# seismometer_sensorboard.net
KiCad netlist of a schematic drawn in EAGLE
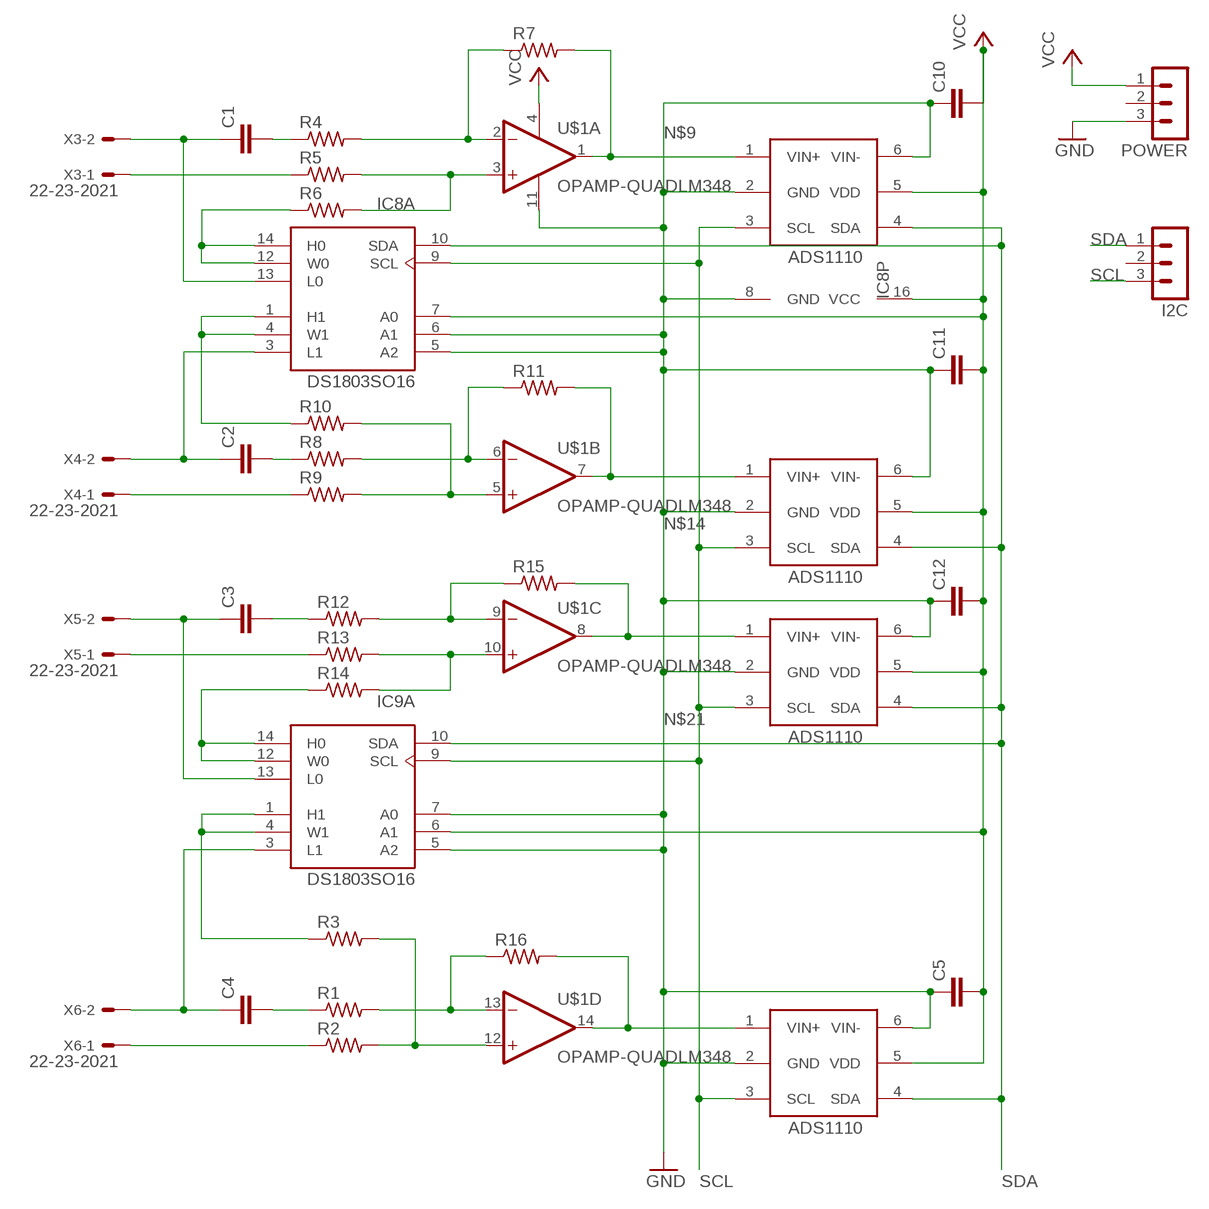
[diagram p0: schematic, sheet 1]

(export (version "E")
  (design (tool "Eeschema 10.0.6"))
  (components
    (comp (ref "C1")
      (value "C-EU025-030X050")
      (footprint "eagle-import:C025-030X050")
      (libsource (lib "eagle-import") (part "C-EU025-030X050"))
    )
    (comp (ref "C2")
      (value "C-EU025-030X050")
      (footprint "eagle-import:C025-030X050")
      (libsource (lib "eagle-import") (part "C-EU025-030X050"))
    )
    (comp (ref "C3")
      (value "C-EU025-030X050")
      (footprint "eagle-import:C025-030X050")
      (libsource (lib "eagle-import") (part "C-EU025-030X050"))
    )
    (comp (ref "C4")
      (value "C-EU025-030X050")
      (footprint "eagle-import:C025-030X050")
      (libsource (lib "eagle-import") (part "C-EU025-030X050"))
    )
    (comp (ref "C5")
      (value "C-EU025-030X050")
      (footprint "eagle-import:C025-030X050")
      (libsource (lib "eagle-import") (part "C-EU025-030X050"))
    )
    (comp (ref "C10")
      (value "C-EU025-030X050")
      (footprint "eagle-import:C025-030X050")
      (libsource (lib "eagle-import") (part "C-EU025-030X050"))
    )
    (comp (ref "C11")
      (value "C-EU025-030X050")
      (footprint "eagle-import:C025-030X050")
      (libsource (lib "eagle-import") (part "C-EU025-030X050"))
    )
    (comp (ref "C12")
      (value "C-EU025-030X050")
      (footprint "eagle-import:C025-030X050")
      (libsource (lib "eagle-import") (part "C-EU025-030X050"))
    )
    (comp (ref "I2C")
      (value "MA03-1")
      (footprint "eagle-import:MA03-1")
      (libsource (lib "eagle-import") (part "MA03-1"))
    )
    (comp (ref "IC1")
      (value "ADS1110")
      (footprint "eagle-import:SOT-23-6")
      (libsource (lib "eagle-import") (part "ADS1110"))
    )
    (comp (ref "IC4")
      (value "ADS1110")
      (footprint "eagle-import:SOT-23-6")
      (libsource (lib "eagle-import") (part "ADS1110"))
    )
    (comp (ref "IC5")
      (value "ADS1110")
      (footprint "eagle-import:SOT-23-6")
      (libsource (lib "eagle-import") (part "ADS1110"))
    )
    (comp (ref "IC6")
      (value "ADS1110")
      (footprint "eagle-import:SOT-23-6")
      (libsource (lib "eagle-import") (part "ADS1110"))
    )
    (comp (ref "IC8")
      (value "DS1803SO16")
      (footprint "eagle-import:SO16")
      (libsource (lib "eagle-import") (part "DS1803?SO16"))
    )
    (comp (ref "IC9")
      (value "DS1803SO16")
      (footprint "eagle-import:SO16")
      (libsource (lib "eagle-import") (part "DS1803?SO16"))
    )
    (comp (ref "POWER")
      (value "MA03-1")
      (footprint "eagle-import:MA03-1")
      (libsource (lib "eagle-import") (part "MA03-1"))
    )
    (comp (ref "R1")
      (value "R-US_0207/12")
      (footprint "eagle-import:0207_12")
      (libsource (lib "eagle-import") (part "R-US_0207/12"))
    )
    (comp (ref "R2")
      (value "R-US_0207/12")
      (footprint "eagle-import:0207_12")
      (libsource (lib "eagle-import") (part "R-US_0207/12"))
    )
    (comp (ref "R3")
      (value "R-US_0207/12")
      (footprint "eagle-import:0207_12")
      (libsource (lib "eagle-import") (part "R-US_0207/12"))
    )
    (comp (ref "R4")
      (value "R-US_0207/12")
      (footprint "eagle-import:0207_12")
      (libsource (lib "eagle-import") (part "R-US_0207/12"))
    )
    (comp (ref "R5")
      (value "R-US_0207/12")
      (footprint "eagle-import:0207_12")
      (libsource (lib "eagle-import") (part "R-US_0207/12"))
    )
    (comp (ref "R6")
      (value "R-US_0207/12")
      (footprint "eagle-import:0207_12")
      (libsource (lib "eagle-import") (part "R-US_0207/12"))
    )
    (comp (ref "R7")
      (value "R-US_0207/12")
      (footprint "eagle-import:0207_12")
      (libsource (lib "eagle-import") (part "R-US_0207/12"))
    )
    (comp (ref "R8")
      (value "R-US_0207/12")
      (footprint "eagle-import:0207_12")
      (libsource (lib "eagle-import") (part "R-US_0207/12"))
    )
    (comp (ref "R9")
      (value "R-US_0207/12")
      (footprint "eagle-import:0207_12")
      (libsource (lib "eagle-import") (part "R-US_0207/12"))
    )
    (comp (ref "R10")
      (value "R-US_0207/12")
      (footprint "eagle-import:0207_12")
      (libsource (lib "eagle-import") (part "R-US_0207/12"))
    )
    (comp (ref "R11")
      (value "R-US_0207/12")
      (footprint "eagle-import:0207_12")
      (libsource (lib "eagle-import") (part "R-US_0207/12"))
    )
    (comp (ref "R12")
      (value "R-US_0207/12")
      (footprint "eagle-import:0207_12")
      (libsource (lib "eagle-import") (part "R-US_0207/12"))
    )
    (comp (ref "R13")
      (value "R-US_0207/12")
      (footprint "eagle-import:0207_12")
      (libsource (lib "eagle-import") (part "R-US_0207/12"))
    )
    (comp (ref "R14")
      (value "R-US_0207/12")
      (footprint "eagle-import:0207_12")
      (libsource (lib "eagle-import") (part "R-US_0207/12"))
    )
    (comp (ref "R15")
      (value "R-US_0207/12")
      (footprint "eagle-import:0207_12")
      (libsource (lib "eagle-import") (part "R-US_0207/12"))
    )
    (comp (ref "R16")
      (value "R-US_0207/12")
      (footprint "eagle-import:0207_12")
      (libsource (lib "eagle-import") (part "R-US_0207/12"))
    )
    (comp (ref "U$1")
      (value "OPAMP-QUADLM348")
      (footprint "eagle-import:DIP14")
      (libsource (lib "eagle-import") (part "OPAMP-QUADLM348"))
    )
    (comp (ref "X3")
      (value "22-23-2021")
      (footprint "eagle-import:22-23-2021")
      (fields (field (name "MF") "MOLEX"))
      (libsource (lib "eagle-import") (part "22-23-2021"))
    )
    (comp (ref "X4")
      (value "22-23-2021")
      (footprint "eagle-import:22-23-2021")
      (fields (field (name "MF") "MOLEX"))
      (libsource (lib "eagle-import") (part "22-23-2021"))
    )
    (comp (ref "X5")
      (value "22-23-2021")
      (footprint "eagle-import:22-23-2021")
      (fields (field (name "MF") "MOLEX"))
      (libsource (lib "eagle-import") (part "22-23-2021"))
    )
    (comp (ref "X6")
      (value "22-23-2021")
      (footprint "eagle-import:22-23-2021")
      (fields (field (name "MF") "MOLEX"))
      (libsource (lib "eagle-import") (part "22-23-2021"))
    )
  )
  (nets
    (net (code "1") (name "/N$9") (class "Default")
      (node (ref "IC4") (pin "1") (pinfunction "VIN+_1") (pintype "bidirectional"))
      (node (ref "R7") (pin "2") (pinfunction "2_2") (pintype "passive"))
      (node (ref "U$1") (pin "1") (pinfunction "OUT_1") (pintype "output"))
    )
    (net (code "2") (name "/N$14") (class "Default")
      (node (ref "IC5") (pin "1") (pinfunction "VIN+_1") (pintype "bidirectional"))
      (node (ref "R11") (pin "2") (pinfunction "2_2") (pintype "passive"))
      (node (ref "U$1") (pin "7") (pinfunction "OUT_7") (pintype "output"))
    )
    (net (code "3") (name "/N$21") (class "Default")
      (node (ref "IC6") (pin "1") (pinfunction "VIN+_1") (pintype "bidirectional"))
      (node (ref "R15") (pin "2") (pinfunction "2_2") (pintype "passive"))
      (node (ref "U$1") (pin "8") (pinfunction "OUT_8") (pintype "output"))
    )
    (net (code "4") (name "/SCL") (class "Default")
      (node (ref "I2C") (pin "3") (pinfunction "3_3") (pintype "passive"))
      (node (ref "IC1") (pin "3") (pinfunction "SCL_3") (pintype "bidirectional"))
      (node (ref "IC4") (pin "3") (pinfunction "SCL_3") (pintype "bidirectional"))
      (node (ref "IC5") (pin "3") (pinfunction "SCL_3") (pintype "bidirectional"))
      (node (ref "IC6") (pin "3") (pinfunction "SCL_3") (pintype "bidirectional"))
      (node (ref "IC8") (pin "9") (pinfunction "SCL_9") (pintype "input"))
      (node (ref "IC9") (pin "9") (pinfunction "SCL_9") (pintype "input"))
    )
    (net (code "5") (name "/SDA") (class "Default")
      (node (ref "I2C") (pin "1") (pinfunction "1_1") (pintype "passive"))
      (node (ref "IC1") (pin "4") (pinfunction "SDA_4") (pintype "bidirectional"))
      (node (ref "IC4") (pin "4") (pinfunction "SDA_4") (pintype "bidirectional"))
      (node (ref "IC5") (pin "4") (pinfunction "SDA_4") (pintype "bidirectional"))
      (node (ref "IC6") (pin "4") (pinfunction "SDA_4") (pintype "bidirectional"))
      (node (ref "IC8") (pin "10") (pinfunction "SDA_10") (pintype "bidirectional"))
      (node (ref "IC9") (pin "10") (pinfunction "SDA_10") (pintype "bidirectional"))
    )
    (net (code "6") (name "GND") (class "Default")
      (node (ref "C10") (pin "1") (pinfunction "1_1") (pintype "passive"))
      (node (ref "C11") (pin "1") (pinfunction "1_1") (pintype "passive"))
      (node (ref "C12") (pin "1") (pinfunction "1_1") (pintype "passive"))
      (node (ref "C5") (pin "1") (pinfunction "1_1") (pintype "passive"))
      (node (ref "IC1") (pin "2") (pinfunction "GND_2") (pintype "bidirectional"))
      (node (ref "IC1") (pin "6") (pinfunction "VIN-_6") (pintype "bidirectional"))
      (node (ref "IC4") (pin "2") (pinfunction "GND_2") (pintype "bidirectional"))
      (node (ref "IC4") (pin "6") (pinfunction "VIN-_6") (pintype "bidirectional"))
      (node (ref "IC5") (pin "2") (pinfunction "GND_2") (pintype "bidirectional"))
      (node (ref "IC5") (pin "6") (pinfunction "VIN-_6") (pintype "bidirectional"))
      (node (ref "IC6") (pin "2") (pinfunction "GND_2") (pintype "bidirectional"))
      (node (ref "IC6") (pin "6") (pinfunction "VIN-_6") (pintype "bidirectional"))
      (node (ref "IC8") (pin "5") (pinfunction "A2_5") (pintype "input"))
      (node (ref "IC8") (pin "6") (pinfunction "A1_6") (pintype "input"))
      (node (ref "IC8") (pin "8") (pinfunction "GND_8") (pintype "power_in"))
      (node (ref "IC9") (pin "5") (pinfunction "A2_5") (pintype "input"))
      (node (ref "IC9") (pin "7") (pinfunction "A0_7") (pintype "input"))
      (node (ref "POWER") (pin "3") (pinfunction "3_3") (pintype "passive"))
      (node (ref "U$1") (pin "11") (pinfunction "VEE_11") (pintype "power_in"))
    )
    (net (code "7") (name "Net-(C1-Pad2)") (class "Default")
      (node (ref "C1") (pin "2") (pinfunction "2_2") (pintype "passive"))
      (node (ref "R4") (pin "1") (pinfunction "1_1") (pintype "passive"))
    )
    (net (code "8") (name "Net-(C2-Pad2)") (class "Default")
      (node (ref "C2") (pin "2") (pinfunction "2_2") (pintype "passive"))
      (node (ref "R8") (pin "1") (pinfunction "1_1") (pintype "passive"))
    )
    (net (code "9") (name "Net-(C3-Pad2)") (class "Default")
      (node (ref "C3") (pin "2") (pinfunction "2_2") (pintype "passive"))
      (node (ref "R12") (pin "1") (pinfunction "1_1") (pintype "passive"))
    )
    (net (code "10") (name "Net-(C4-Pad2)") (class "Default")
      (node (ref "C4") (pin "2") (pinfunction "2_2") (pintype "passive"))
      (node (ref "R1") (pin "1") (pinfunction "1_1") (pintype "passive"))
    )
    (net (code "11") (name "Net-(IC1-VIN+)") (class "Default")
      (node (ref "IC1") (pin "1") (pinfunction "VIN+_1") (pintype "bidirectional"))
      (node (ref "R16") (pin "2") (pinfunction "2_2") (pintype "passive"))
      (node (ref "U$1") (pin "14") (pinfunction "OUT_14") (pintype "output"))
    )
    (net (code "12") (name "Net-(IC8A-H0)") (class "Default")
      (node (ref "IC8") (pin "12") (pinfunction "W0_12") (pintype "bidirectional"))
      (node (ref "IC8") (pin "14") (pinfunction "H0_14") (pintype "bidirectional"))
      (node (ref "R6") (pin "1") (pinfunction "1_1") (pintype "passive"))
    )
    (net (code "13") (name "Net-(IC8A-H1)") (class "Default")
      (node (ref "IC8") (pin "1") (pinfunction "H1_1") (pintype "bidirectional"))
      (node (ref "IC8") (pin "4") (pinfunction "W1_4") (pintype "bidirectional"))
      (node (ref "R10") (pin "1") (pinfunction "1_1") (pintype "passive"))
    )
    (net (code "14") (name "Net-(IC8A-L0)") (class "Default")
      (node (ref "C1") (pin "1") (pinfunction "1_1") (pintype "passive"))
      (node (ref "IC8") (pin "13") (pinfunction "L0_13") (pintype "bidirectional"))
      (node (ref "X3") (pin "2") (pinfunction "S_2") (pintype "passive"))
    )
    (net (code "15") (name "Net-(IC8A-L1)") (class "Default")
      (node (ref "C2") (pin "1") (pinfunction "1_1") (pintype "passive"))
      (node (ref "IC8") (pin "3") (pinfunction "L1_3") (pintype "bidirectional"))
      (node (ref "X4") (pin "2") (pinfunction "S_2") (pintype "passive"))
    )
    (net (code "16") (name "Net-(IC9A-H0)") (class "Default")
      (node (ref "IC9") (pin "12") (pinfunction "W0_12") (pintype "bidirectional"))
      (node (ref "IC9") (pin "14") (pinfunction "H0_14") (pintype "bidirectional"))
      (node (ref "R14") (pin "1") (pinfunction "1_1") (pintype "passive"))
    )
    (net (code "17") (name "Net-(IC9A-H1)") (class "Default")
      (node (ref "IC9") (pin "1") (pinfunction "H1_1") (pintype "bidirectional"))
      (node (ref "IC9") (pin "4") (pinfunction "W1_4") (pintype "bidirectional"))
      (node (ref "R3") (pin "1") (pinfunction "1_1") (pintype "passive"))
    )
    (net (code "18") (name "Net-(IC9A-L0)") (class "Default")
      (node (ref "C3") (pin "1") (pinfunction "1_1") (pintype "passive"))
      (node (ref "IC9") (pin "13") (pinfunction "L0_13") (pintype "bidirectional"))
      (node (ref "X5") (pin "2") (pinfunction "S_2") (pintype "passive"))
    )
    (net (code "19") (name "Net-(IC9A-L1)") (class "Default")
      (node (ref "C4") (pin "1") (pinfunction "1_1") (pintype "passive"))
      (node (ref "IC9") (pin "3") (pinfunction "L1_3") (pintype "bidirectional"))
      (node (ref "X6") (pin "2") (pinfunction "S_2") (pintype "passive"))
    )
    (net (code "20") (name "Net-(U$1A-IN+)") (class "Default")
      (node (ref "R5") (pin "2") (pinfunction "2_2") (pintype "passive"))
      (node (ref "R6") (pin "2") (pinfunction "2_2") (pintype "passive"))
      (node (ref "U$1") (pin "3") (pinfunction "IN+_3") (pintype "input"))
    )
    (net (code "21") (name "Net-(U$1A-IN-)") (class "Default")
      (node (ref "R4") (pin "2") (pinfunction "2_2") (pintype "passive"))
      (node (ref "R7") (pin "1") (pinfunction "1_1") (pintype "passive"))
      (node (ref "U$1") (pin "2") (pinfunction "IN-_2") (pintype "input"))
    )
    (net (code "22") (name "Net-(U$1B-IN+)") (class "Default")
      (node (ref "R10") (pin "2") (pinfunction "2_2") (pintype "passive"))
      (node (ref "R9") (pin "2") (pinfunction "2_2") (pintype "passive"))
      (node (ref "U$1") (pin "5") (pinfunction "IN+_5") (pintype "input"))
    )
    (net (code "23") (name "Net-(U$1B-IN-)") (class "Default")
      (node (ref "R11") (pin "1") (pinfunction "1_1") (pintype "passive"))
      (node (ref "R8") (pin "2") (pinfunction "2_2") (pintype "passive"))
      (node (ref "U$1") (pin "6") (pinfunction "IN-_6") (pintype "input"))
    )
    (net (code "24") (name "Net-(U$1C-IN+)") (class "Default")
      (node (ref "R13") (pin "2") (pinfunction "2_2") (pintype "passive"))
      (node (ref "R14") (pin "2") (pinfunction "2_2") (pintype "passive"))
      (node (ref "U$1") (pin "10") (pinfunction "IN+_10") (pintype "input"))
    )
    (net (code "25") (name "Net-(U$1C-IN-)") (class "Default")
      (node (ref "R12") (pin "2") (pinfunction "2_2") (pintype "passive"))
      (node (ref "R15") (pin "1") (pinfunction "1_1") (pintype "passive"))
      (node (ref "U$1") (pin "9") (pinfunction "IN-_9") (pintype "input"))
    )
    (net (code "26") (name "Net-(U$1D-IN+)") (class "Default")
      (node (ref "R2") (pin "2") (pinfunction "2_2") (pintype "passive"))
      (node (ref "R3") (pin "2") (pinfunction "2_2") (pintype "passive"))
      (node (ref "U$1") (pin "12") (pinfunction "IN+_12") (pintype "input"))
    )
    (net (code "27") (name "Net-(U$1D-IN-)") (class "Default")
      (node (ref "R1") (pin "2") (pinfunction "2_2") (pintype "passive"))
      (node (ref "R16") (pin "1") (pinfunction "1_1") (pintype "passive"))
      (node (ref "U$1") (pin "13") (pinfunction "IN-_13") (pintype "input"))
    )
    (net (code "28") (name "Net-(X3A-S)") (class "Default")
      (node (ref "R5") (pin "1") (pinfunction "1_1") (pintype "passive"))
      (node (ref "X3") (pin "1") (pinfunction "S_1") (pintype "passive"))
    )
    (net (code "29") (name "Net-(X4A-S)") (class "Default")
      (node (ref "R9") (pin "1") (pinfunction "1_1") (pintype "passive"))
      (node (ref "X4") (pin "1") (pinfunction "S_1") (pintype "passive"))
    )
    (net (code "30") (name "Net-(X5A-S)") (class "Default")
      (node (ref "R13") (pin "1") (pinfunction "1_1") (pintype "passive"))
      (node (ref "X5") (pin "1") (pinfunction "S_1") (pintype "passive"))
    )
    (net (code "31") (name "Net-(X6A-S)") (class "Default")
      (node (ref "R2") (pin "1") (pinfunction "1_1") (pintype "passive"))
      (node (ref "X6") (pin "1") (pinfunction "S_1") (pintype "passive"))
    )
    (net (code "32") (name "VCC") (class "Default")
      (node (ref "C10") (pin "2") (pinfunction "2_2") (pintype "passive"))
      (node (ref "C11") (pin "2") (pinfunction "2_2") (pintype "passive"))
      (node (ref "C12") (pin "2") (pinfunction "2_2") (pintype "passive"))
      (node (ref "C5") (pin "2") (pinfunction "2_2") (pintype "passive"))
      (node (ref "IC1") (pin "5") (pinfunction "VDD_5") (pintype "bidirectional"))
      (node (ref "IC4") (pin "5") (pinfunction "VDD_5") (pintype "bidirectional"))
      (node (ref "IC5") (pin "5") (pinfunction "VDD_5") (pintype "bidirectional"))
      (node (ref "IC6") (pin "5") (pinfunction "VDD_5") (pintype "bidirectional"))
      (node (ref "IC8") (pin "16") (pinfunction "VCC_16") (pintype "power_in"))
      (node (ref "IC8") (pin "7") (pinfunction "A0_7") (pintype "input"))
      (node (ref "IC9") (pin "6") (pinfunction "A1_6") (pintype "input"))
      (node (ref "POWER") (pin "1") (pinfunction "1_1") (pintype "passive"))
      (node (ref "U$1") (pin "4") (pinfunction "VCC_4") (pintype "power_in"))
    )
    (net (code "33") (name "unconnected-(I2C-Pad2)") (class "Default")
      (node (ref "I2C") (pin "2") (pinfunction "2_2") (pintype "passive"))
    )
    (net (code "34") (name "unconnected-(POWER-Pad2)") (class "Default")
      (node (ref "POWER") (pin "2") (pinfunction "2_2") (pintype "passive"))
    )
  )
)
